# SDR1806.net
KiCad netlist of a schematic drawn in EAGLE
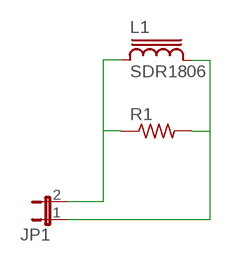
[diagram p0: schematic, sheet 1]

(export (version "E")
  (design (tool "Eeschema 10.0.6"))
  (components
    (comp (ref "JP1")
      (value "JP1E")
      (footprint "eagle-import:JP1")
      (libsource (lib "eagle-import") (part "JP1E"))
    )
    (comp (ref "L1")
      (value "SDR1806")
      (footprint "eagle-import:SDR1806")
      (libsource (lib "eagle-import") (part "SDR1806"))
    )
    (comp (ref "R1")
      (value "R-US_R0603")
      (footprint "eagle-import:R0603")
      (libsource (lib "eagle-import") (part "R-US_R0603"))
    )
  )
  (nets
    (net (code "1") (name "Net-(JP1-Pad1)") (class "Default")
      (node (ref "JP1") (pin "1") (pinfunction "1_1") (pintype "passive"))
      (node (ref "L1") (pin "2") (pinfunction "2_2") (pintype "passive"))
      (node (ref "R1") (pin "2") (pinfunction "2_2") (pintype "passive"))
    )
    (net (code "2") (name "Net-(JP1-Pad2)") (class "Default")
      (node (ref "JP1") (pin "2") (pinfunction "2_2") (pintype "passive"))
      (node (ref "L1") (pin "1") (pinfunction "1_1") (pintype "passive"))
      (node (ref "R1") (pin "1") (pinfunction "1_1") (pintype "passive"))
    )
  )
)
